# 24LC00T_EEPROM.net
KiCad netlist of a schematic drawn in Altium Designer
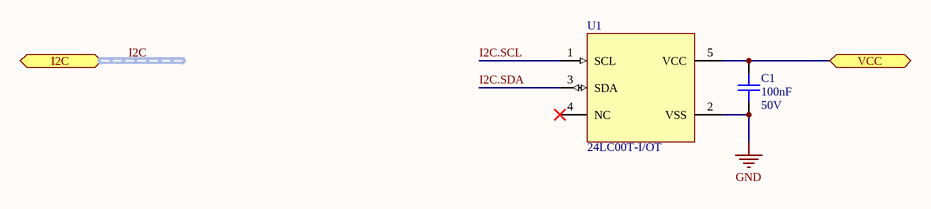
[diagram p0: 24LC00T_EEPROM.SchDoc]

(export (version "E")
  (design (tool "Eeschema 10.0.6"))
  (components
    (comp (ref "C1")
      (value "CAP CER 0.1UF 50V X7R 0402")
      (footprint "C0402")
      (description "0.1µF ±10% 50V Ceramic Capacitor X7R 0402 (1005 Metric)")
      (fields
        (field (name "MANUFACTURER PART NUMBER") "CGA2B3X7R1H104K050BB")
        (field (name "MANUFACTURER") "TDK")
        (field (name "CAPACITANCE") "100nF")
        (field (name "VOLTAGE") "50V")
      )
      (libsource (lib "capacitors_smd") (part "CAP CER 0.1UF 50V X7R 0402"))
    )
    (comp (ref "U1")
      (value "24LC00T-I/OT")
      (footprint "SOT-23-5")
      (description "EEPROM Memory IC 128b (16 x 8) I²C 400kHz 3500ns SOT-23-5")
      (fields (field (name "MANUFACTURER") "Microchip"))
      (libsource (lib "BLDC_Motor_Driver") (part "IC 24LC00T-I/OT EEPROM 128 I2C SOT23-5"))
    )
  )
  (nets
    (net (code "2") (name "/I2C.SCL") (class "Default")
      (node (ref "U1") (pin "1") (pinfunction "SCL_1") (pintype "input"))
    )
    (net (code "3") (name "/I2C.SDA") (class "Default")
      (node (ref "U1") (pin "3") (pinfunction "SDA_3") (pintype "bidirectional"))
    )
    (net (code "4") (name "/VCC") (class "Default")
      (node (ref "C1") (pin "2") (pinfunction "2_2") (pintype "passive"))
      (node (ref "U1") (pin "5") (pinfunction "VCC_5") (pintype "power_in"))
    )
    (net (code "6") (name "GND") (class "Default")
      (node (ref "C1") (pin "1") (pinfunction "1_1") (pintype "passive"))
      (node (ref "U1") (pin "2") (pinfunction "VSS_2") (pintype "power_in"))
    )
    (net (code "7") (name "unconnected-(U1-NC-Pad4)") (class "Default")
      (node (ref "U1") (pin "4") (pinfunction "NC_4") (pintype "passive+no_connect"))
    )
  )
)
